# wt901c__2026-02-21.net
KiCad netlist of a schematic drawn in EasyEDA Pro
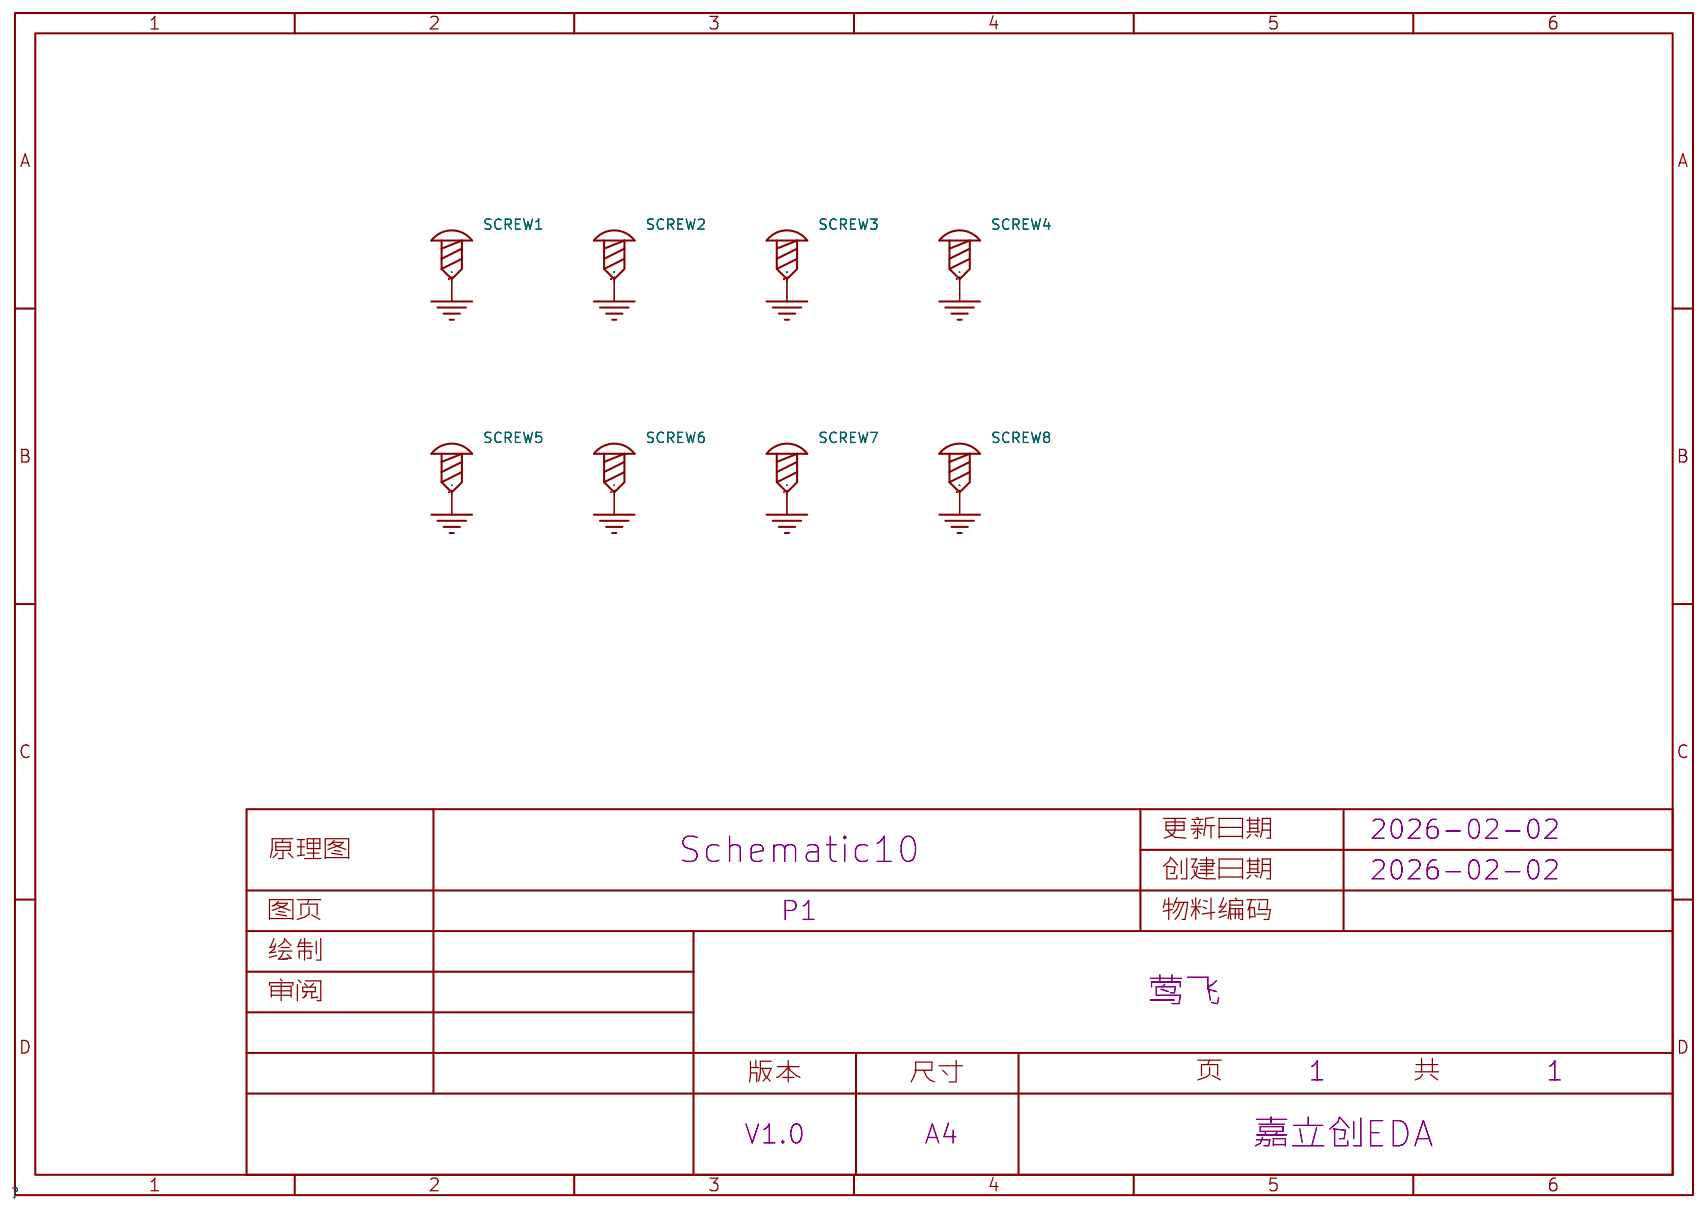
[diagram p0: schematic sheet]

(export (version "E")
  (design (tool "Eeschema 10.0.6"))
  (components
    (comp (ref "SCREW1")
      (value "~")
      (footprint "easyedapro:M3螺丝")
      (libsource (lib "easyedapro") (part "螺丝孔_3"))
    )
    (comp (ref "SCREW2")
      (value "~")
      (footprint "easyedapro:M3螺丝")
      (libsource (lib "easyedapro") (part "螺丝孔_3"))
    )
    (comp (ref "SCREW3")
      (value "~")
      (footprint "easyedapro:M3螺丝")
      (libsource (lib "easyedapro") (part "螺丝孔_3"))
    )
    (comp (ref "SCREW4")
      (value "~")
      (footprint "easyedapro:M3螺丝")
      (libsource (lib "easyedapro") (part "螺丝孔_3"))
    )
    (comp (ref "SCREW5")
      (value "~")
      (footprint "easyedapro:M3螺丝")
      (libsource (lib "easyedapro") (part "螺丝孔_3"))
    )
    (comp (ref "SCREW6")
      (value "~")
      (footprint "easyedapro:M3螺丝")
      (libsource (lib "easyedapro") (part "螺丝孔_3"))
    )
    (comp (ref "SCREW7")
      (value "~")
      (footprint "easyedapro:M3螺丝")
      (libsource (lib "easyedapro") (part "螺丝孔_3"))
    )
    (comp (ref "SCREW8")
      (value "~")
      (footprint "easyedapro:M3螺丝")
      (libsource (lib "easyedapro") (part "螺丝孔_3"))
    )
  )
  (nets
    (net (code "1") (name "GND") (class "Default")
      (node (ref "SCREW1") (pin "1") (pinfunction "1_1") (pintype "input"))
      (node (ref "SCREW2") (pin "1") (pinfunction "1_1") (pintype "input"))
      (node (ref "SCREW3") (pin "1") (pinfunction "1_1") (pintype "input"))
      (node (ref "SCREW4") (pin "1") (pinfunction "1_1") (pintype "input"))
      (node (ref "SCREW5") (pin "1") (pinfunction "1_1") (pintype "input"))
      (node (ref "SCREW6") (pin "1") (pinfunction "1_1") (pintype "input"))
      (node (ref "SCREW7") (pin "1") (pinfunction "1_1") (pintype "input"))
      (node (ref "SCREW8") (pin "1") (pinfunction "1_1") (pintype "input"))
    )
  )
)
